# blink_tutorial.net
KiCad netlist of a schematic drawn in EAGLE
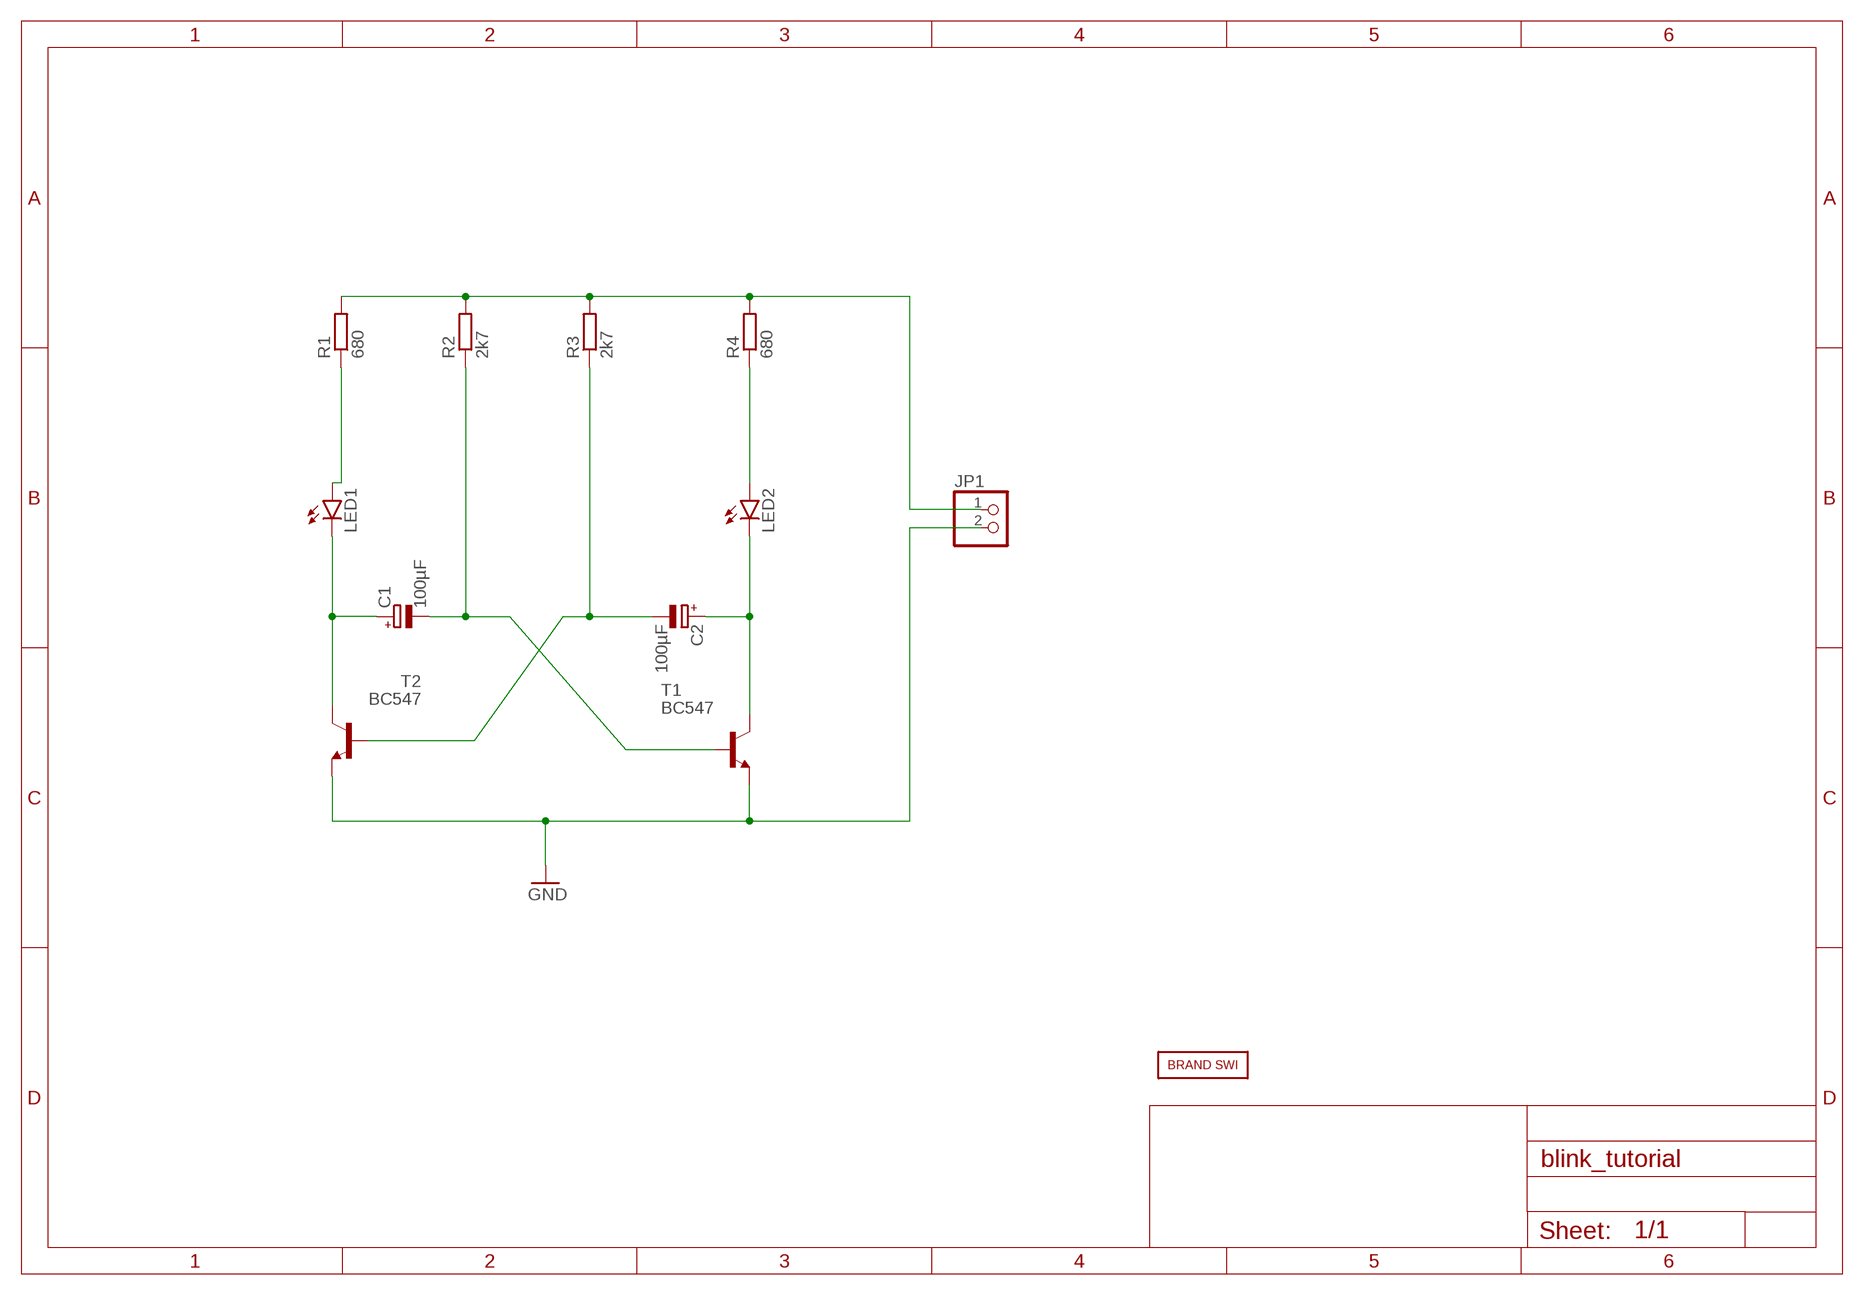
[diagram p0: schematic, sheet 1]

(export (version "E")
  (design (tool "Eeschema 10.0.6"))
  (components
    (comp (ref "C1")
      (value "100µF")
      (footprint "eagle-import:E2,5-6")
      (libsource (lib "eagle-import") (part "CPOL-EUE2.5-6"))
    )
    (comp (ref "C2")
      (value "100µF")
      (footprint "eagle-import:E2,5-6")
      (libsource (lib "eagle-import") (part "CPOL-EUE2.5-6"))
    )
    (comp (ref "JP1")
      (value "PINHD-1X2")
      (footprint "eagle-import:1X02")
      (libsource (lib "eagle-import") (part "PINHD-1X2"))
    )
    (comp (ref "LED1")
      (value "LED5MM")
      (footprint "eagle-import:LED5MM")
      (libsource (lib "eagle-import") (part "LED5MM"))
    )
    (comp (ref "LED2")
      (value "LED5MM")
      (footprint "eagle-import:LED5MM")
      (libsource (lib "eagle-import") (part "LED5MM"))
    )
    (comp (ref "R1")
      (value "680")
      (footprint "eagle-import:M1206")
      (libsource (lib "eagle-import") (part "R-EU_M1206"))
    )
    (comp (ref "R2")
      (value "2k7")
      (footprint "eagle-import:M1206")
      (libsource (lib "eagle-import") (part "R-EU_M1206"))
    )
    (comp (ref "R3")
      (value "2k7")
      (footprint "eagle-import:M1206")
      (libsource (lib "eagle-import") (part "R-EU_M1206"))
    )
    (comp (ref "R4")
      (value "680")
      (footprint "eagle-import:M1206")
      (libsource (lib "eagle-import") (part "R-EU_M1206"))
    )
    (comp (ref "T1")
      (value "BC547")
      (footprint "eagle-import:TO92")
      (libsource (lib "eagle-import") (part "BC547"))
    )
    (comp (ref "T2")
      (value "BC547")
      (footprint "eagle-import:TO92")
      (libsource (lib "eagle-import") (part "BC547"))
    )
    (comp (ref "U$1")
      (value "SIG1")
      (footprint "eagle-import:BRAND_SWI_5X7")
      (libsource (lib "eagle-import") (part "BRAND_SWI5X7"))
    )
  )
  (nets
    (net (code "1") (name "GND") (class "Default")
      (node (ref "JP1") (pin "2") (pinfunction "2_2") (pintype "passive"))
      (node (ref "T1") (pin "1") (pinfunction "E_1") (pintype "passive"))
      (node (ref "T2") (pin "1") (pinfunction "E_1") (pintype "passive"))
    )
    (net (code "2") (name "Net-(JP1-Pad1)") (class "Default")
      (node (ref "JP1") (pin "1") (pinfunction "1_1") (pintype "passive"))
      (node (ref "R1") (pin "2") (pinfunction "2_2") (pintype "passive"))
      (node (ref "R2") (pin "2") (pinfunction "2_2") (pintype "passive"))
      (node (ref "R3") (pin "2") (pinfunction "2_2") (pintype "passive"))
      (node (ref "R4") (pin "2") (pinfunction "2_2") (pintype "passive"))
    )
    (net (code "3") (name "Net-(LED1-C)") (class "Default")
      (node (ref "C1") (pin "+") (pinfunction "+_+") (pintype "passive"))
      (node (ref "LED1") (pin "K") (pinfunction "C_K") (pintype "passive"))
      (node (ref "T2") (pin "3") (pinfunction "C_3") (pintype "passive"))
    )
    (net (code "4") (name "Net-(LED1-PadA)") (class "Default")
      (node (ref "LED1") (pin "A") (pinfunction "A_A") (pintype "passive"))
      (node (ref "R1") (pin "1") (pinfunction "1_1") (pintype "passive"))
    )
    (net (code "5") (name "Net-(LED2-C)") (class "Default")
      (node (ref "C2") (pin "+") (pinfunction "+_+") (pintype "passive"))
      (node (ref "LED2") (pin "K") (pinfunction "C_K") (pintype "passive"))
      (node (ref "T1") (pin "3") (pinfunction "C_3") (pintype "passive"))
    )
    (net (code "6") (name "Net-(LED2-PadA)") (class "Default")
      (node (ref "LED2") (pin "A") (pinfunction "A_A") (pintype "passive"))
      (node (ref "R4") (pin "1") (pinfunction "1_1") (pintype "passive"))
    )
    (net (code "7") (name "Net-(T1-B)") (class "Default")
      (node (ref "C1") (pin "-") (pinfunction "-_-") (pintype "passive"))
      (node (ref "R2") (pin "1") (pinfunction "1_1") (pintype "passive"))
      (node (ref "T1") (pin "2") (pinfunction "B_2") (pintype "passive"))
    )
    (net (code "8") (name "Net-(T2-B)") (class "Default")
      (node (ref "C2") (pin "-") (pinfunction "-_-") (pintype "passive"))
      (node (ref "R3") (pin "1") (pinfunction "1_1") (pintype "passive"))
      (node (ref "T2") (pin "2") (pinfunction "B_2") (pintype "passive"))
    )
  )
)
